# PowerControlExpansion.net
KiCad netlist of a schematic drawn in EAGLE
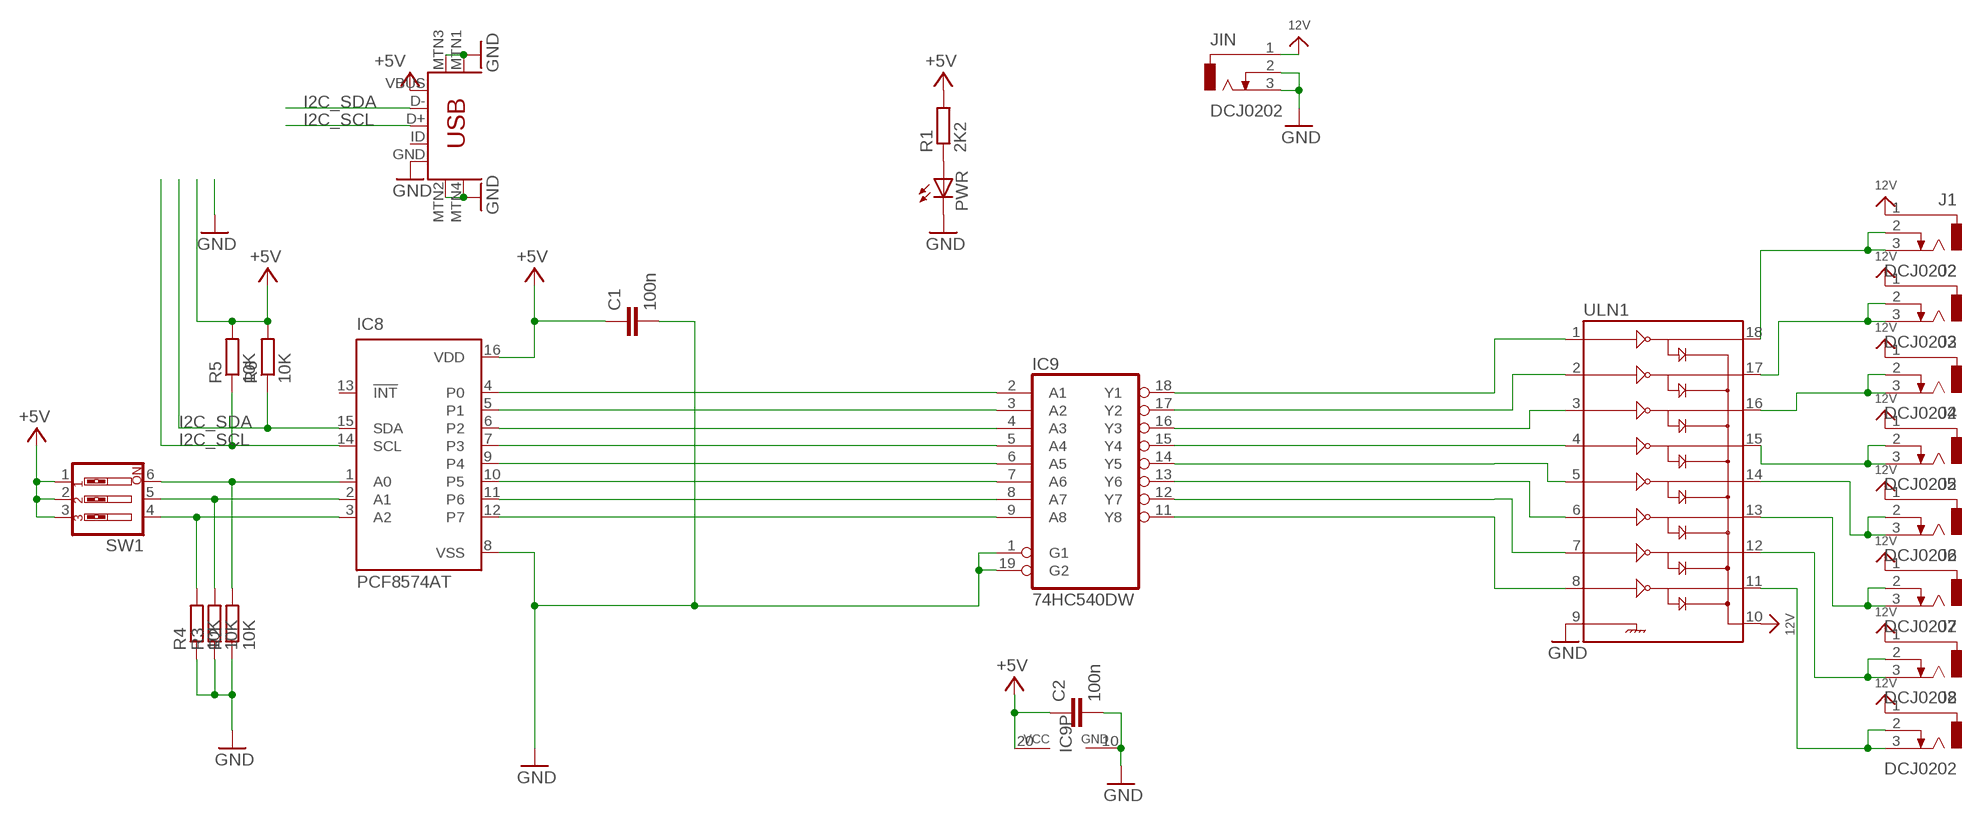
[diagram p0: schematic, sheet 1]

(export (version "E")
  (design (tool "Eeschema 10.0.6"))
  (components
    (comp (ref "C1")
      (value "100n")
      (footprint "eagle-import:C0805K")
      (libsource (lib "eagle-import") (part "C-EUC0805K"))
    )
    (comp (ref "C2")
      (value "100n")
      (footprint "eagle-import:C0805K")
      (libsource (lib "eagle-import") (part "C-EUC0805K"))
    )
    (comp (ref "IC8")
      (value "PCF8574AT")
      (footprint "eagle-import:SO16W")
      (libsource (lib "eagle-import") (part "PCF8574T"))
    )
    (comp (ref "IC9")
      (value "74HC540DW")
      (footprint "eagle-import:SO20W")
      (libsource (lib "eagle-import") (part "74540DWHC"))
    )
    (comp (ref "J1")
      (value "DCJ0202")
      (footprint "eagle-import:DCJ0202")
      (fields (field (name "OC_FARNELL") "unknown") (field (name "OC_NEWARK") "unknown"))
      (libsource (lib "eagle-import") (part "DCJ0202"))
    )
    (comp (ref "J2")
      (value "DCJ0202")
      (footprint "eagle-import:DCJ0202")
      (fields (field (name "OC_FARNELL") "unknown") (field (name "OC_NEWARK") "unknown"))
      (libsource (lib "eagle-import") (part "DCJ0202"))
    )
    (comp (ref "J3")
      (value "DCJ0202")
      (footprint "eagle-import:DCJ0202")
      (fields (field (name "OC_FARNELL") "unknown") (field (name "OC_NEWARK") "unknown"))
      (libsource (lib "eagle-import") (part "DCJ0202"))
    )
    (comp (ref "J4")
      (value "DCJ0202")
      (footprint "eagle-import:DCJ0202")
      (fields (field (name "OC_FARNELL") "unknown") (field (name "OC_NEWARK") "unknown"))
      (libsource (lib "eagle-import") (part "DCJ0202"))
    )
    (comp (ref "J5")
      (value "DCJ0202")
      (footprint "eagle-import:DCJ0202")
      (fields (field (name "OC_FARNELL") "unknown") (field (name "OC_NEWARK") "unknown"))
      (libsource (lib "eagle-import") (part "DCJ0202"))
    )
    (comp (ref "J6")
      (value "DCJ0202")
      (footprint "eagle-import:DCJ0202")
      (fields (field (name "OC_FARNELL") "unknown") (field (name "OC_NEWARK") "unknown"))
      (libsource (lib "eagle-import") (part "DCJ0202"))
    )
    (comp (ref "J7")
      (value "DCJ0202")
      (footprint "eagle-import:DCJ0202")
      (fields (field (name "OC_FARNELL") "unknown") (field (name "OC_NEWARK") "unknown"))
      (libsource (lib "eagle-import") (part "DCJ0202"))
    )
    (comp (ref "J8")
      (value "DCJ0202")
      (footprint "eagle-import:DCJ0202")
      (fields (field (name "OC_FARNELL") "unknown") (field (name "OC_NEWARK") "unknown"))
      (libsource (lib "eagle-import") (part "DCJ0202"))
    )
    (comp (ref "JIN")
      (value "DCJ0202")
      (footprint "eagle-import:DCJ0202")
      (libsource (lib "eagle-import") (part "DCJ0202"))
    )
    (comp (ref "PWR")
      (value "LED3MM")
      (footprint "eagle-import:LED3MM")
      (libsource (lib "eagle-import") (part "LED3MM"))
    )
    (comp (ref "R1")
      (value "2K2")
      (footprint "eagle-import:R0805W")
      (libsource (lib "eagle-import") (part "R-EU_R0805W"))
    )
    (comp (ref "R2")
      (value "10K")
      (footprint "eagle-import:R0805W")
      (libsource (lib "eagle-import") (part "R-EU_R0805W"))
    )
    (comp (ref "R3")
      (value "10K")
      (footprint "eagle-import:R0805W")
      (libsource (lib "eagle-import") (part "R-EU_R0805W"))
    )
    (comp (ref "R4")
      (value "10K")
      (footprint "eagle-import:R0805W")
      (libsource (lib "eagle-import") (part "R-EU_R0805W"))
    )
    (comp (ref "R5")
      (value "10K")
      (footprint "eagle-import:R0805W")
      (libsource (lib "eagle-import") (part "R-EU_R0805W"))
    )
    (comp (ref "R6")
      (value "10K")
      (footprint "eagle-import:R0805W")
      (libsource (lib "eagle-import") (part "R-EU_R0805W"))
    )
    (comp (ref "SW1")
      (value "SW_DIP-3")
      (footprint "eagle-import:EDG-03")
      (libsource (lib "eagle-import") (part "SW_DIP-3"))
    )
    (comp (ref "U1")
      (value "USB-MINIB-5PIN")
      (footprint "eagle-import:USB-MINIB")
      (libsource (lib "eagle-import") (part "USB-MINIB-5PIN"))
    )
    (comp (ref "ULN1")
      (value "ULN2803SOICW")
      (footprint "eagle-import:SO18L")
      (libsource (lib "eagle-import") (part "ULN2803SOICW"))
    )
  )
  (nets
    (net (code "1") (name "+5V") (class "Default")
      (node (ref "C1") (pin "1") (pinfunction "1_1") (pintype "passive"))
      (node (ref "C2") (pin "1") (pinfunction "1_1") (pintype "passive"))
      (node (ref "IC8") (pin "16") (pinfunction "VDD_16") (pintype "power_in"))
      (node (ref "IC9") (pin "20") (pinfunction "VCC_20") (pintype "power_in"))
      (node (ref "R1") (pin "2") (pinfunction "2_2") (pintype "passive"))
      (node (ref "R5") (pin "2") (pinfunction "2_2") (pintype "passive"))
      (node (ref "R6") (pin "2") (pinfunction "2_2") (pintype "passive"))
      (node (ref "SW1") (pin "1") (pinfunction "1_1") (pintype "passive"))
      (node (ref "SW1") (pin "2") (pinfunction "2_2") (pintype "passive"))
      (node (ref "SW1") (pin "3") (pinfunction "3_3") (pintype "passive"))
      (node (ref "U1") (pin "VBUS") (pinfunction "VBUS_VBUS") (pintype "bidirectional"))
    )
    (net (code "2") (name "/I2C_SCL") (class "Default")
      (node (ref "IC8") (pin "14") (pinfunction "SCL_14") (pintype "input"))
      (node (ref "R5") (pin "1") (pinfunction "1_1") (pintype "passive"))
      (node (ref "U1") (pin "D+") (pinfunction "D+_D+") (pintype "bidirectional"))
    )
    (net (code "3") (name "/I2C_SDA") (class "Default")
      (node (ref "IC8") (pin "15") (pinfunction "SDA_15") (pintype "bidirectional"))
      (node (ref "R6") (pin "1") (pinfunction "1_1") (pintype "passive"))
      (node (ref "U1") (pin "D-") (pinfunction "D-_D-") (pintype "bidirectional"))
    )
    (net (code "4") (name "12V") (class "Default")
      (node (ref "J1") (pin "1") (pinfunction "1_1") (pintype "passive"))
      (node (ref "J2") (pin "1") (pinfunction "1_1") (pintype "passive"))
      (node (ref "J3") (pin "1") (pinfunction "1_1") (pintype "passive"))
      (node (ref "J4") (pin "1") (pinfunction "1_1") (pintype "passive"))
      (node (ref "J5") (pin "1") (pinfunction "1_1") (pintype "passive"))
      (node (ref "J6") (pin "1") (pinfunction "1_1") (pintype "passive"))
      (node (ref "J7") (pin "1") (pinfunction "1_1") (pintype "passive"))
      (node (ref "J8") (pin "1") (pinfunction "1_1") (pintype "passive"))
      (node (ref "JIN") (pin "1") (pinfunction "1_1") (pintype "passive"))
      (node (ref "ULN1") (pin "10") (pinfunction "10_10") (pintype "bidirectional"))
    )
    (net (code "5") (name "GND") (class "Default")
      (node (ref "C1") (pin "2") (pinfunction "2_2") (pintype "passive"))
      (node (ref "C2") (pin "2") (pinfunction "2_2") (pintype "passive"))
      (node (ref "IC8") (pin "8") (pinfunction "VSS_8") (pintype "power_in"))
      (node (ref "IC9") (pin "1") (pinfunction "G1_1") (pintype "input"))
      (node (ref "IC9") (pin "10") (pinfunction "GND_10") (pintype "power_in"))
      (node (ref "IC9") (pin "19") (pinfunction "G2_19") (pintype "input"))
      (node (ref "JIN") (pin "2") (pinfunction "2_2") (pintype "passive"))
      (node (ref "JIN") (pin "3") (pinfunction "3_3") (pintype "passive"))
      (node (ref "PWR") (pin "K") (pinfunction "C_K") (pintype "passive"))
      (node (ref "R2") (pin "1") (pinfunction "1_1") (pintype "passive"))
      (node (ref "R3") (pin "1") (pinfunction "1_1") (pintype "passive"))
      (node (ref "R4") (pin "1") (pinfunction "1_1") (pintype "passive"))
      (node (ref "U1") (pin "GND") (pinfunction "GND_GND") (pintype "bidirectional"))
      (node (ref "U1") (pin "MTN1") (pinfunction "MTN2_MTN1") (pintype "bidirectional"))
      (node (ref "U1") (pin "MTN2") (pinfunction "MTN3_MTN2") (pintype "bidirectional"))
      (node (ref "U1") (pin "MTN3") (pinfunction "MTN1_MTN3") (pintype "bidirectional"))
      (node (ref "U1") (pin "MTN4") (pinfunction "MTN4_MTN4") (pintype "bidirectional"))
      (node (ref "ULN1") (pin "9") (pinfunction "9_9") (pintype "bidirectional"))
    )
    (net (code "6") (name "Net-(IC8-A0)") (class "Default")
      (node (ref "IC8") (pin "1") (pinfunction "A0_1") (pintype "input"))
      (node (ref "R2") (pin "2") (pinfunction "2_2") (pintype "passive"))
      (node (ref "SW1") (pin "6") (pinfunction "6_6") (pintype "passive"))
    )
    (net (code "7") (name "Net-(IC8-A1)") (class "Default")
      (node (ref "IC8") (pin "2") (pinfunction "A1_2") (pintype "input"))
      (node (ref "R3") (pin "2") (pinfunction "2_2") (pintype "passive"))
      (node (ref "SW1") (pin "5") (pinfunction "5_5") (pintype "passive"))
    )
    (net (code "8") (name "Net-(IC8-A2)") (class "Default")
      (node (ref "IC8") (pin "3") (pinfunction "A2_3") (pintype "input"))
      (node (ref "R4") (pin "2") (pinfunction "2_2") (pintype "passive"))
      (node (ref "SW1") (pin "4") (pinfunction "4_4") (pintype "passive"))
    )
    (net (code "9") (name "Net-(IC8-P0)") (class "Default")
      (node (ref "IC8") (pin "4") (pinfunction "P0_4") (pintype "bidirectional"))
      (node (ref "IC9") (pin "2") (pinfunction "A1_2") (pintype "input"))
    )
    (net (code "10") (name "Net-(IC8-P1)") (class "Default")
      (node (ref "IC8") (pin "5") (pinfunction "P1_5") (pintype "bidirectional"))
      (node (ref "IC9") (pin "3") (pinfunction "A2_3") (pintype "input"))
    )
    (net (code "11") (name "Net-(IC8-P2)") (class "Default")
      (node (ref "IC8") (pin "6") (pinfunction "P2_6") (pintype "bidirectional"))
      (node (ref "IC9") (pin "4") (pinfunction "A3_4") (pintype "input"))
    )
    (net (code "12") (name "Net-(IC8-P3)") (class "Default")
      (node (ref "IC8") (pin "7") (pinfunction "P3_7") (pintype "bidirectional"))
      (node (ref "IC9") (pin "5") (pinfunction "A4_5") (pintype "input"))
    )
    (net (code "13") (name "Net-(IC8-P4)") (class "Default")
      (node (ref "IC8") (pin "9") (pinfunction "P4_9") (pintype "bidirectional"))
      (node (ref "IC9") (pin "6") (pinfunction "A5_6") (pintype "input"))
    )
    (net (code "14") (name "Net-(IC8-P5)") (class "Default")
      (node (ref "IC8") (pin "10") (pinfunction "P5_10") (pintype "bidirectional"))
      (node (ref "IC9") (pin "7") (pinfunction "A6_7") (pintype "input"))
    )
    (net (code "15") (name "Net-(IC8-P6)") (class "Default")
      (node (ref "IC8") (pin "11") (pinfunction "P6_11") (pintype "bidirectional"))
      (node (ref "IC9") (pin "8") (pinfunction "A7_8") (pintype "input"))
    )
    (net (code "16") (name "Net-(IC8-P7)") (class "Default")
      (node (ref "IC8") (pin "12") (pinfunction "P7_12") (pintype "bidirectional"))
      (node (ref "IC9") (pin "9") (pinfunction "A8_9") (pintype "input"))
    )
    (net (code "17") (name "Net-(IC9A-Y1)") (class "Default")
      (node (ref "IC9") (pin "18") (pinfunction "Y1_18") (pintype "tri_state"))
      (node (ref "ULN1") (pin "1") (pinfunction "1_1") (pintype "bidirectional"))
    )
    (net (code "18") (name "Net-(IC9A-Y2)") (class "Default")
      (node (ref "IC9") (pin "17") (pinfunction "Y2_17") (pintype "tri_state"))
      (node (ref "ULN1") (pin "2") (pinfunction "2_2") (pintype "bidirectional"))
    )
    (net (code "19") (name "Net-(IC9A-Y3)") (class "Default")
      (node (ref "IC9") (pin "16") (pinfunction "Y3_16") (pintype "tri_state"))
      (node (ref "ULN1") (pin "3") (pinfunction "3_3") (pintype "bidirectional"))
    )
    (net (code "20") (name "Net-(IC9A-Y4)") (class "Default")
      (node (ref "IC9") (pin "15") (pinfunction "Y4_15") (pintype "tri_state"))
      (node (ref "ULN1") (pin "4") (pinfunction "4_4") (pintype "bidirectional"))
    )
    (net (code "21") (name "Net-(IC9A-Y5)") (class "Default")
      (node (ref "IC9") (pin "14") (pinfunction "Y5_14") (pintype "tri_state"))
      (node (ref "ULN1") (pin "5") (pinfunction "5_5") (pintype "bidirectional"))
    )
    (net (code "22") (name "Net-(IC9A-Y6)") (class "Default")
      (node (ref "IC9") (pin "13") (pinfunction "Y6_13") (pintype "tri_state"))
      (node (ref "ULN1") (pin "6") (pinfunction "6_6") (pintype "bidirectional"))
    )
    (net (code "23") (name "Net-(IC9A-Y7)") (class "Default")
      (node (ref "IC9") (pin "12") (pinfunction "Y7_12") (pintype "tri_state"))
      (node (ref "ULN1") (pin "7") (pinfunction "7_7") (pintype "bidirectional"))
    )
    (net (code "24") (name "Net-(IC9A-Y8)") (class "Default")
      (node (ref "IC9") (pin "11") (pinfunction "Y8_11") (pintype "tri_state"))
      (node (ref "ULN1") (pin "8") (pinfunction "8_8") (pintype "bidirectional"))
    )
    (net (code "25") (name "Net-(J1-Pad2)") (class "Default")
      (node (ref "J1") (pin "2") (pinfunction "2_2") (pintype "passive"))
      (node (ref "J1") (pin "3") (pinfunction "3_3") (pintype "passive"))
      (node (ref "ULN1") (pin "18") (pinfunction "18_18") (pintype "bidirectional"))
    )
    (net (code "26") (name "Net-(J2-Pad2)") (class "Default")
      (node (ref "J2") (pin "2") (pinfunction "2_2") (pintype "passive"))
      (node (ref "J2") (pin "3") (pinfunction "3_3") (pintype "passive"))
      (node (ref "ULN1") (pin "17") (pinfunction "17_17") (pintype "bidirectional"))
    )
    (net (code "27") (name "Net-(J3-Pad2)") (class "Default")
      (node (ref "J3") (pin "2") (pinfunction "2_2") (pintype "passive"))
      (node (ref "J3") (pin "3") (pinfunction "3_3") (pintype "passive"))
      (node (ref "ULN1") (pin "16") (pinfunction "16_16") (pintype "bidirectional"))
    )
    (net (code "28") (name "Net-(J4-Pad2)") (class "Default")
      (node (ref "J4") (pin "2") (pinfunction "2_2") (pintype "passive"))
      (node (ref "J4") (pin "3") (pinfunction "3_3") (pintype "passive"))
      (node (ref "ULN1") (pin "15") (pinfunction "15_15") (pintype "bidirectional"))
    )
    (net (code "29") (name "Net-(J5-Pad2)") (class "Default")
      (node (ref "J5") (pin "2") (pinfunction "2_2") (pintype "passive"))
      (node (ref "J5") (pin "3") (pinfunction "3_3") (pintype "passive"))
      (node (ref "ULN1") (pin "14") (pinfunction "14_14") (pintype "bidirectional"))
    )
    (net (code "30") (name "Net-(J6-Pad2)") (class "Default")
      (node (ref "J6") (pin "2") (pinfunction "2_2") (pintype "passive"))
      (node (ref "J6") (pin "3") (pinfunction "3_3") (pintype "passive"))
      (node (ref "ULN1") (pin "13") (pinfunction "13_13") (pintype "bidirectional"))
    )
    (net (code "31") (name "Net-(J7-Pad2)") (class "Default")
      (node (ref "J7") (pin "2") (pinfunction "2_2") (pintype "passive"))
      (node (ref "J7") (pin "3") (pinfunction "3_3") (pintype "passive"))
      (node (ref "ULN1") (pin "12") (pinfunction "12_12") (pintype "bidirectional"))
    )
    (net (code "32") (name "Net-(J8-Pad2)") (class "Default")
      (node (ref "J8") (pin "2") (pinfunction "2_2") (pintype "passive"))
      (node (ref "J8") (pin "3") (pinfunction "3_3") (pintype "passive"))
      (node (ref "ULN1") (pin "11") (pinfunction "11_11") (pintype "bidirectional"))
    )
    (net (code "33") (name "Net-(PWR-PadA)") (class "Default")
      (node (ref "PWR") (pin "A") (pinfunction "A_A") (pintype "passive"))
      (node (ref "R1") (pin "1") (pinfunction "1_1") (pintype "passive"))
    )
    (net (code "34") (name "unconnected-(IC8-~{INT}-Pad13)") (class "Default")
      (node (ref "IC8") (pin "13") (pinfunction "~{INT}_13") (pintype "output"))
    )
    (net (code "35") (name "unconnected-(U1-PadID)") (class "Default")
      (node (ref "U1") (pin "ID") (pinfunction "ID_ID") (pintype "bidirectional"))
    )
  )
)
